# PowerSupply.net
KiCad netlist of a schematic drawn in Altium Designer
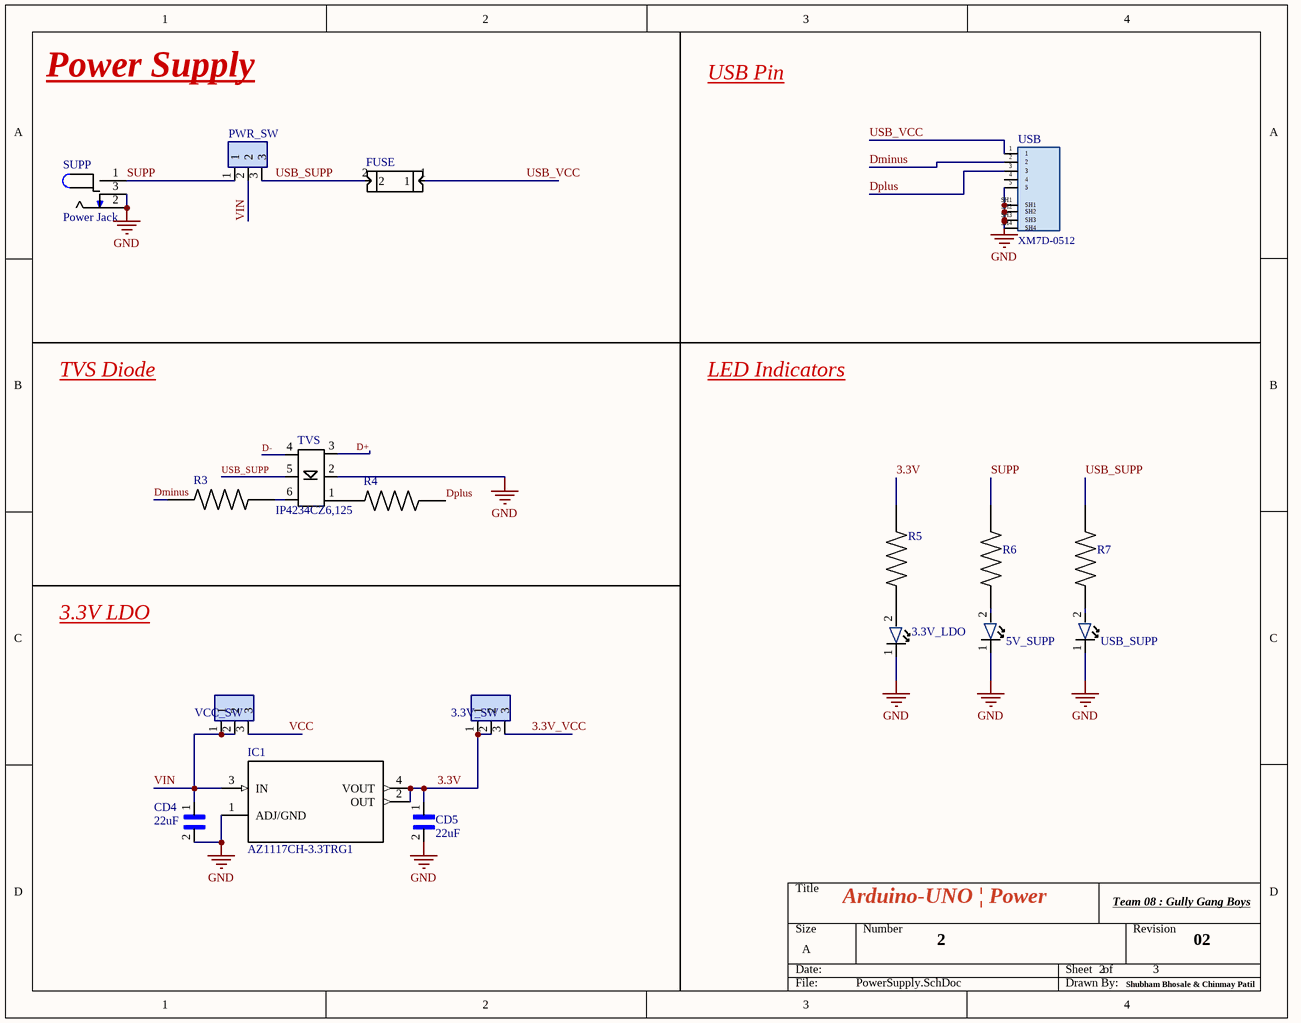
[diagram p0: PowerSupply.SchDoc]

(export (version "E")
  (design (tool "Eeschema 10.0.6"))
  (components
    (comp (ref "3.3V_LDO")
      (value "LTST-C150CKT")
      (footprint "LED")
      (description "Red 638nm LED Indication - Discrete 1.8V 1206 (3216 Metric)")
      (fields (field (name "DIGIKEY PART") "160-1167-1-ND"))
      (libsource (lib "brd2_rev2") (part "1206_RED_LED"))
    )
    (comp (ref "3.3V_SW")
      (value "PREC003SAAN-RC")
      (footprint "3_PIN")
      (description "Connector Header Through Hole 3 position 0.100\" (2.54mm)")
      (fields (field (name "DIGIKEY PART") "S1012EC-03-ND"))
      (libsource (lib "brd2_rev2") (part "3_PIN"))
    )
    (comp (ref "5V_SUPP")
      (value "LTST-C150CKT")
      (footprint "LED")
      (description "Red 638nm LED Indication - Discrete 1.8V 1206 (3216 Metric)")
      (fields (field (name "DIGIKEY PART") "160-1167-1-ND"))
      (libsource (lib "brd2_rev2") (part "1206_RED_LED"))
    )
    (comp (ref "CD4")
      (value "22uF")
      (footprint "1206_Passive")
      (description "22µF ±20% 16V Ceramic Capacitor X5R 1206 (3216 Metric)")
      (fields (field (name "DIGIKEY PART") "1276-2728-1-ND"))
      (libsource (lib "brd2_rev2") (part "1206_22uF"))
    )
    (comp (ref "CD5")
      (value "22uF")
      (footprint "1206_Passive")
      (description "22µF ±20% 16V Ceramic Capacitor X5R 1206 (3216 Metric)")
      (fields (field (name "DIGIKEY PART") "1276-2728-1-ND"))
      (libsource (lib "brd2_rev2") (part "1206_22uF"))
    )
    (comp (ref "FUSE")
      (value "MF-MSMF050-2")
      (footprint "FUSE")
      (description "Polymeric PTC Resettable Fuse 15V 500mA Ih Surface Mount 1812 (4532 Metric), Concave")
      (fields (field (name "DIGIKEY PART") "MF-MSMF050-2CT-ND"))
      (libsource (lib "brd2_rev2") (part "Fuse"))
    )
    (comp (ref "IC1")
      (value "AZ1117CH-3.3TRG1")
      (footprint "LDO")
      (description "Linear Voltage Regulator IC Positive Fixed 1 Output 1A SOT-223")
      (fields (field (name "DIGIKEY PART") "AZ1117CH-3.3TRG1DICT-ND"))
      (libsource (lib "brd2_rev2") (part "3.3V_LDO"))
    )
    (comp (ref "PWR_SW")
      (value "PREC003SAAN-RC")
      (footprint "3_PIN")
      (description "Connector Header Through Hole 3 position 0.100\" (2.54mm)")
      (fields (field (name "DIGIKEY PART") "S1012EC-03-ND"))
      (libsource (lib "brd2_rev2") (part "3_PIN"))
    )
    (comp (ref "R3")
      (value "RMCF1206JT300R‎")
      (footprint "1206_Passive")
      (description "300 Ohms ±5% 0.25W, 1/4W Chip Resistor 1206 (3216 Metric) Automotive AEC-Q200 Thick Film")
      (fields (field (name "DIGIKEY PART") "RMCF1206JT300RCT-ND"))
      (libsource (lib "brd2_rev2") (part "1206_300Ohm"))
    )
    (comp (ref "R4")
      (value "RMCF1206JT300R‎")
      (footprint "1206_Passive")
      (description "300 Ohms ±5% 0.25W, 1/4W Chip Resistor 1206 (3216 Metric) Automotive AEC-Q200 Thick Film")
      (fields (field (name "DIGIKEY PART") "RMCF1206JT300RCT-ND"))
      (libsource (lib "brd2_rev2") (part "1206_300Ohm"))
    )
    (comp (ref "R5")
      (value "RNCP1206FTD1K00")
      (footprint "1206_Passive")
      (description "1 kOhms ±1% 0.5W, 1/2W Chip Resistor 1206 (3216 Metric) Anti-Sulfur, Moisture Resistant Thin Film")
      (fields (field (name "DIGIKEY PART") "RNCP1206FTD1K00CT-ND"))
      (libsource (lib "brd2_rev2") (part "1206_1K"))
    )
    (comp (ref "R6")
      (value "RNCP1206FTD1K00")
      (footprint "1206_Passive")
      (description "1 kOhms ±1% 0.5W, 1/2W Chip Resistor 1206 (3216 Metric) Anti-Sulfur, Moisture Resistant Thin Film")
      (fields (field (name "DIGIKEY PART") "RNCP1206FTD1K00CT-ND"))
      (libsource (lib "brd2_rev2") (part "1206_1K"))
    )
    (comp (ref "R7")
      (value "RNCP1206FTD1K00")
      (footprint "1206_Passive")
      (description "1 kOhms ±1% 0.5W, 1/2W Chip Resistor 1206 (3216 Metric) Anti-Sulfur, Moisture Resistant Thin Film")
      (fields (field (name "DIGIKEY PART") "RNCP1206FTD1K00CT-ND"))
      (libsource (lib "brd2_rev2") (part "1206_1K"))
    )
    (comp (ref "SUPP")
      (value "Power Jack")
      (footprint "Power_Jack")
      (description "Power Barrel Connector Jack 2.10mm ID (0.083\"), 5.50mm OD (0.217\") Through Hole, Right Angle")
      (fields (field (name "DIGIKEY PART") "CP-102A-ND"))
      (libsource (lib "brd2_rev2") (part "Power Jack"))
    )
    (comp (ref "TVS")
      (value "IP4234CZ6,125")
      (footprint "TVS")
      (description "Clamp Ipp Tvs Diode Surface Mount 6-TSOP")
      (fields (field (name "DIGIKEY PART") "1727-4717-1-ND"))
      (libsource (lib "brd2_rev2") (part "TVS_Diode"))
    )
    (comp (ref "USB")
      (value "XM7D-0512")
      (footprint "USB")
      (description "USB - mini B USB 2.0 Receptacle Connector 5 Position Through Hole, Right Angle")
      (fields (field (name "DIGIKEY PART") "OR1205-ND"))
      (libsource (lib "brd2_rev2") (part "USB"))
    )
    (comp (ref "USB_SUPP")
      (value "LTST-C150CKT")
      (footprint "LED")
      (description "Red 638nm LED Indication - Discrete 1.8V 1206 (3216 Metric)")
      (fields (field (name "DIGIKEY PART") "160-1167-1-ND"))
      (libsource (lib "brd2_rev2") (part "1206_RED_LED"))
    )
    (comp (ref "VCC_SW")
      (value "PREC003SAAN-RC")
      (footprint "3_PIN")
      (description "Connector Header Through Hole 3 position 0.100\" (2.54mm)")
      (fields (field (name "DIGIKEY PART") "S1012EC-03-ND"))
      (libsource (lib "brd2_rev2") (part "3_PIN"))
    )
  )
  (nets
    (net (code "1") (name "/3.3V") (class "Default")
      (node (ref "3.3V_SW") (pin "1") (pinfunction "1_1") (pintype "passive"))
      (node (ref "3.3V_SW") (pin "2") (pinfunction "2_2") (pintype "passive"))
      (node (ref "CD5") (pin "1") (pinfunction "1_1") (pintype "passive"))
      (node (ref "IC1") (pin "2") (pinfunction "OUT_2") (pintype "output"))
      (node (ref "IC1") (pin "4") (pinfunction "VOUT_4") (pintype "output"))
      (node (ref "R5") (pin "2") (pinfunction "2_2") (pintype "passive"))
    )
    (net (code "2") (name "/3.3V_VCC") (class "Default")
      (node (ref "3.3V_SW") (pin "3") (pinfunction "3_3") (pintype "passive"))
    )
    (net (code "4") (name "/D+") (class "Default")
      (node (ref "TVS") (pin "3") (pinfunction "3_3") (pintype "passive"))
    )
    (net (code "5") (name "/D-") (class "Default")
      (node (ref "TVS") (pin "4") (pinfunction "4_4") (pintype "passive"))
    )
    (net (code "6") (name "/Dminus") (class "Default")
      (node (ref "R3") (pin "1") (pinfunction "1_1") (pintype "passive"))
      (node (ref "USB") (pin "2") (pinfunction "2_2") (pintype "passive"))
    )
    (net (code "7") (name "/Dplus") (class "Default")
      (node (ref "R4") (pin "2") (pinfunction "2_2") (pintype "passive"))
      (node (ref "USB") (pin "3") (pinfunction "3_3") (pintype "passive"))
    )
    (net (code "8") (name "/SUPP") (class "Default")
      (node (ref "PWR_SW") (pin "1") (pinfunction "1_1") (pintype "passive"))
      (node (ref "R6") (pin "1") (pinfunction "1_1") (pintype "passive"))
      (node (ref "SUPP") (pin "1") (pinfunction "1_1") (pintype "passive"))
    )
    (net (code "9") (name "/USB_SUPP") (class "Default")
      (node (ref "FUSE") (pin "2") (pinfunction "2_2") (pintype "passive"))
      (node (ref "PWR_SW") (pin "3") (pinfunction "3_3") (pintype "passive"))
      (node (ref "R7") (pin "1") (pinfunction "1_1") (pintype "passive"))
      (node (ref "TVS") (pin "5") (pinfunction "5_5") (pintype "passive"))
    )
    (net (code "10") (name "/USB_VCC") (class "Default")
      (node (ref "FUSE") (pin "1") (pinfunction "1_1") (pintype "passive"))
      (node (ref "USB") (pin "1") (pinfunction "1_1") (pintype "passive"))
    )
    (net (code "11") (name "/VCC") (class "Default")
      (node (ref "VCC_SW") (pin "3") (pinfunction "3_3") (pintype "passive"))
    )
    (net (code "12") (name "/VIN") (class "Default")
      (node (ref "CD4") (pin "1") (pinfunction "1_1") (pintype "passive"))
      (node (ref "IC1") (pin "3") (pinfunction "IN_3") (pintype "input"))
      (node (ref "PWR_SW") (pin "2") (pinfunction "2_2") (pintype "passive"))
      (node (ref "VCC_SW") (pin "1") (pinfunction "1_1") (pintype "passive"))
      (node (ref "VCC_SW") (pin "2") (pinfunction "2_2") (pintype "passive"))
    )
    (net (code "13") (name "GND") (class "Default")
      (node (ref "3.3V_LDO") (pin "1") (pinfunction "1_1") (pintype "passive"))
      (node (ref "5V_SUPP") (pin "1") (pinfunction "1_1") (pintype "passive"))
      (node (ref "CD4") (pin "2") (pinfunction "2_2") (pintype "passive"))
      (node (ref "CD5") (pin "2") (pinfunction "2_2") (pintype "passive"))
      (node (ref "IC1") (pin "1") (pinfunction "ADJ/GND_1") (pintype "passive"))
      (node (ref "SUPP") (pin "2") (pinfunction "2_2") (pintype "passive"))
      (node (ref "SUPP") (pin "3") (pinfunction "3_3") (pintype "passive"))
      (node (ref "TVS") (pin "2") (pinfunction "2_2") (pintype "passive"))
      (node (ref "USB") (pin "5") (pinfunction "5_5") (pintype "passive"))
      (node (ref "USB") (pin "SH1") (pinfunction "SH1_SH1") (pintype "passive"))
      (node (ref "USB") (pin "SH2") (pinfunction "SH2_SH2") (pintype "passive"))
      (node (ref "USB") (pin "SH3") (pinfunction "SH3_SH3") (pintype "passive"))
      (node (ref "USB") (pin "SH4") (pinfunction "SH4_SH4") (pintype "passive"))
      (node (ref "USB_SUPP") (pin "1") (pinfunction "1_1") (pintype "passive"))
    )
    (net (code "14") (name "Net-(3.3V_LDO-Pad2)") (class "Default")
      (node (ref "3.3V_LDO") (pin "2") (pinfunction "2_2") (pintype "passive"))
      (node (ref "R5") (pin "1") (pinfunction "1_1") (pintype "passive"))
    )
    (net (code "15") (name "Net-(5V_SUPP-Pad2)") (class "Default")
      (node (ref "5V_SUPP") (pin "2") (pinfunction "2_2") (pintype "passive"))
      (node (ref "R6") (pin "2") (pinfunction "2_2") (pintype "passive"))
    )
    (net (code "16") (name "Net-(R3-Pad2)") (class "Default")
      (node (ref "R3") (pin "2") (pinfunction "2_2") (pintype "passive"))
      (node (ref "TVS") (pin "6") (pinfunction "6_6") (pintype "passive"))
    )
    (net (code "17") (name "Net-(R4-Pad1)") (class "Default")
      (node (ref "R4") (pin "1") (pinfunction "1_1") (pintype "passive"))
      (node (ref "TVS") (pin "1") (pinfunction "1_1") (pintype "passive"))
    )
    (net (code "18") (name "Net-(R7-Pad2)") (class "Default")
      (node (ref "R7") (pin "2") (pinfunction "2_2") (pintype "passive"))
      (node (ref "USB_SUPP") (pin "2") (pinfunction "2_2") (pintype "passive"))
    )
    (net (code "19") (name "unconnected-(USB-Pad4)") (class "Default")
      (node (ref "USB") (pin "4") (pinfunction "4_4") (pintype "passive"))
    )
  )
)
